# POWER_LIPO.net
KiCad netlist of a schematic drawn in Altium Designer
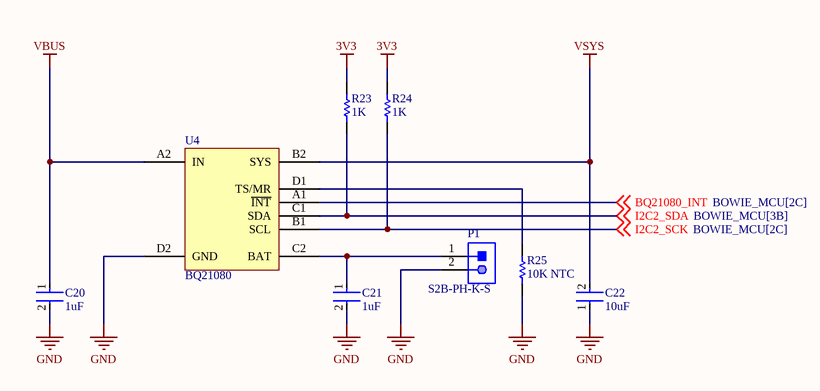
[diagram p0: POWER_LIPO.SchDoc]

(export (version "E")
  (design (tool "Eeschema 10.0.6"))
  (components
    (comp (ref "C20")
      (value "1uF")
      (footprint "FP-0603-L_1_6_0_15-W_0_8-IPC_C")
      (description "Ceramic Capacitor General Use 1uF ±10% 50V X7R 0603")
      (fields (field (name "TOLERANCE") "10%"))
      (libsource (lib "Altium Content Vault") (part "11868f565c42a9108669ba33697ecf6"))
    )
    (comp (ref "C21")
      (value "1uF")
      (footprint "FP-0603-L_1_6_0_15-W_0_8-IPC_C")
      (description "Ceramic Capacitor General Use 1uF ±10% 50V X7R 0603")
      (fields (field (name "TOLERANCE") "10%"))
      (libsource (lib "Altium Content Vault") (part "11868f565c42a9108669ba33697ecf6"))
    )
    (comp (ref "C22")
      (value "10uF")
      (footprint "FP-C1608-080-0_1-MFG")
      (description "Multilayer Ceramic Capacitors 10μF ±10% 10V X5R SMD 0603")
      (fields (field (name "VOLTAGE") "10V") (field (name "TOLERANCE") "10%"))
      (libsource (lib "Altium Content Vault") (part "236180d848d6139a670b325ea6854c9"))
    )
    (comp (ref "P1")
      (value "S2B-PH-K-S")
      (footprint "JST-S2B-PH-K-S_V")
      (fields (field (name "TOLERANCE") "20%"))
      (libsource (lib "Altium Content Vault") (part "CN-1P-M-R2"))
    )
    (comp (ref "R23")
      (value "1K")
      (footprint "RESC1005X40X25NL05T05")
      (description "Chip Resistor, 1 KOhm, +/- 1%, 100 mW, -55 to 155 degC, 0402 (1005 Metric), RoHS, Tape and Reel")
      (fields (field (name "PARTNUMBER") "ERJ-2RKF1001X") (field (name "MANUFACTURER") "Basic Passives"))
      (libsource (lib "Altium Content Vault") (part "RES-2"))
    )
    (comp (ref "R24")
      (value "1K")
      (footprint "RESC1005X40X25NL05T05")
      (description "Chip Resistor, 1 KOhm, +/- 1%, 100 mW, -55 to 155 degC, 0402 (1005 Metric), RoHS, Tape and Reel")
      (fields (field (name "PARTNUMBER") "ERJ-2RKF1001X") (field (name "MANUFACTURER") "Basic Passives"))
      (libsource (lib "Altium Content Vault") (part "RES-2"))
    )
    (comp (ref "R25")
      (value "10K NTC")
      (footprint "RESC1005X40X25NL05T05")
      (fields (field (name "PART NUMBER") "ERT-J0ER103J") (field (name "MANUFACTURER") "Panasonic"))
      (libsource (lib "Altium Content Vault") (part "RES"))
    )
    (comp (ref "U4") (value "BQ21080") (footprint "BQ21080_bga") (libsource (lib "BQ21080") (part "BQ21080")))
  )
  (nets
    (net (code "1") (name "3V3") (class "Default")
      (node (ref "R23") (pin "2") (pinfunction "2_2") (pintype "passive"))
      (node (ref "R24") (pin "2") (pinfunction "2_2") (pintype "passive"))
    )
    (net (code "2") (name "BQ21080_INT") (class "Default")
      (node (ref "U4") (pin "A1") (pinfunction "~{INT}_A1") (pintype "passive"))
    )
    (net (code "3") (name "GND") (class "Default")
      (node (ref "C20") (pin "2") (pinfunction "2_2") (pintype "passive"))
      (node (ref "C21") (pin "2") (pinfunction "2_2") (pintype "passive"))
      (node (ref "C22") (pin "1") (pinfunction "1_1") (pintype "passive"))
      (node (ref "P1") (pin "2") (pinfunction "2_2") (pintype "passive"))
      (node (ref "R25") (pin "1") (pinfunction "1_1") (pintype "passive"))
      (node (ref "U4") (pin "D2") (pinfunction "GND_D2") (pintype "passive"))
    )
    (net (code "4") (name "I2C2_SCK") (class "Default")
      (node (ref "R24") (pin "1") (pinfunction "1_1") (pintype "passive"))
      (node (ref "U4") (pin "B1") (pinfunction "SCL_B1") (pintype "passive"))
    )
    (net (code "5") (name "I2C2_SDA") (class "Default")
      (node (ref "R23") (pin "1") (pinfunction "1_1") (pintype "passive"))
      (node (ref "U4") (pin "C1") (pinfunction "SDA_C1") (pintype "passive"))
    )
    (net (code "6") (name "Net-(U4-BAT)") (class "Default")
      (node (ref "C21") (pin "1") (pinfunction "1_1") (pintype "passive"))
      (node (ref "P1") (pin "1") (pinfunction "1_1") (pintype "passive"))
      (node (ref "U4") (pin "C2") (pinfunction "BAT_C2") (pintype "passive"))
    )
    (net (code "7") (name "Net-(U4-TS{slash}MR)") (class "Default")
      (node (ref "R25") (pin "2") (pinfunction "2_2") (pintype "passive"))
      (node (ref "U4") (pin "D1") (pinfunction "TS/MR_D1") (pintype "passive"))
    )
    (net (code "8") (name "VBUS") (class "Default")
      (node (ref "C20") (pin "1") (pinfunction "1_1") (pintype "passive"))
      (node (ref "U4") (pin "A2") (pinfunction "IN_A2") (pintype "passive"))
    )
    (net (code "9") (name "VSYS") (class "Default")
      (node (ref "C22") (pin "2") (pinfunction "2_2") (pintype "passive"))
      (node (ref "U4") (pin "B2") (pinfunction "SYS_B2") (pintype "passive"))
    )
  )
)
